# ATX_Adapter.net
KiCad netlist of a schematic drawn in EAGLE
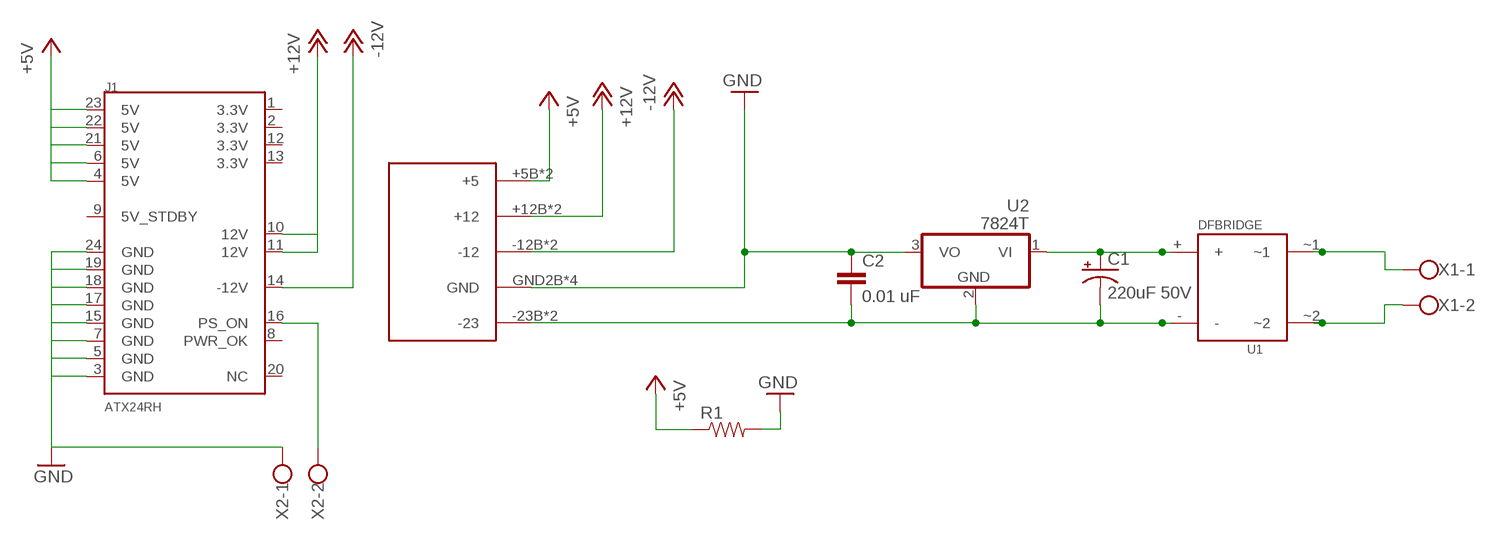
[diagram p0: schematic, sheet 1]

(export (version "E")
  (design (tool "Eeschema 10.0.6"))
  (components
    (comp (ref "C1")
      (value "220uF 50V")
      (footprint "eagle-import:CPOL-RADIAL-100UF-25V")
      (libsource (lib "eagle-import") (part "CAP_POLPTH1"))
    )
    (comp (ref "C2")
      (value "0.01 uF")
      (footprint "eagle-import:CAP-PTH-SMALLEZ")
      (libsource (lib "eagle-import") (part "CAPEZ"))
    )
    (comp (ref "J1")
      (value "ATX24RH")
      (footprint "eagle-import:ATX24_RIGHT_ANGLE")
      (libsource (lib "eagle-import") (part "ATX24RH"))
    )
    (comp (ref "R1")
      (value "RESISTORPTH-2W")
      (footprint "eagle-import:AXIAL-0.8")
      (libsource (lib "eagle-import") (part "RESISTORPTH-2W"))
    )
    (comp (ref "U$1")
      (value "VT100POWER")
      (footprint "eagle-import:VT100POWER")
      (libsource (lib "eagle-import") (part "VT100POWER"))
    )
    (comp (ref "U1")
      (value "DFBRIDGE")
      (footprint "eagle-import:DFBRIDGE")
      (libsource (lib "eagle-import") (part "DFBRIDGE"))
    )
    (comp (ref "U2")
      (value "7824T")
      (footprint "eagle-import:TO220H")
      (libsource (lib "eagle-import") (part "78T24"))
    )
    (comp (ref "X1")
      (value "W237-102")
      (footprint "eagle-import:W237-102")
      (fields (field (name "MPN") "237-102"))
      (libsource (lib "eagle-import") (part "W237-102"))
    )
    (comp (ref "X2")
      (value "W237-102")
      (footprint "eagle-import:W237-102")
      (fields (field (name "MPN") "237-102"))
      (libsource (lib "eagle-import") (part "W237-102"))
    )
  )
  (nets
    (net (code "1") (name "+5V") (class "Default")
      (node (ref "J1") (pin "21") (pinfunction "5V_21") (pintype "bidirectional"))
      (node (ref "J1") (pin "22") (pinfunction "5V_22") (pintype "bidirectional"))
      (node (ref "J1") (pin "23") (pinfunction "5V_23") (pintype "bidirectional"))
      (node (ref "J1") (pin "4") (pinfunction "5V_4") (pintype "bidirectional"))
      (node (ref "J1") (pin "6") (pinfunction "5V_6") (pintype "bidirectional"))
      (node (ref "R1") (pin "P$1") (pinfunction "1_P$1") (pintype "passive"))
      (node (ref "U$1") (pin "+5B") (pinfunction "+5_+5B") (pintype "bidirectional"))
      (node (ref "U$1") (pin "+5T") (pinfunction "+5_+5T") (pintype "bidirectional"))
    )
    (net (code "2") (name "+12V") (class "Default")
      (node (ref "J1") (pin "10") (pinfunction "12V_10") (pintype "bidirectional"))
      (node (ref "J1") (pin "11") (pinfunction "12V_11") (pintype "bidirectional"))
      (node (ref "U$1") (pin "+12B") (pinfunction "+12_+12B") (pintype "bidirectional"))
      (node (ref "U$1") (pin "+12T") (pinfunction "+12_+12T") (pintype "bidirectional"))
    )
    (net (code "3") (name "-12V") (class "Default")
      (node (ref "J1") (pin "14") (pinfunction "-12V_14") (pintype "bidirectional"))
      (node (ref "U$1") (pin "-12B") (pinfunction "-12_-12B") (pintype "bidirectional"))
      (node (ref "U$1") (pin "-12T") (pinfunction "-12_-12T") (pintype "bidirectional"))
    )
    (net (code "4") (name "GND") (class "Default")
      (node (ref "C2") (pin "1") (pinfunction "1_1") (pintype "passive"))
      (node (ref "J1") (pin "15") (pinfunction "GND_15") (pintype "bidirectional"))
      (node (ref "J1") (pin "17") (pinfunction "GND_17") (pintype "bidirectional"))
      (node (ref "J1") (pin "18") (pinfunction "GND_18") (pintype "bidirectional"))
      (node (ref "J1") (pin "19") (pinfunction "GND_19") (pintype "bidirectional"))
      (node (ref "J1") (pin "24") (pinfunction "GND_24") (pintype "bidirectional"))
      (node (ref "J1") (pin "3") (pinfunction "GND_3") (pintype "bidirectional"))
      (node (ref "J1") (pin "5") (pinfunction "GND_5") (pintype "bidirectional"))
      (node (ref "J1") (pin "7") (pinfunction "GND_7") (pintype "bidirectional"))
      (node (ref "R1") (pin "P$2") (pinfunction "2_P$2") (pintype "passive"))
      (node (ref "U$1") (pin "GND2B") (pinfunction "GND_GND2B") (pintype "bidirectional"))
      (node (ref "U$1") (pin "GNDB1") (pinfunction "GND_GNDB1") (pintype "bidirectional"))
      (node (ref "U$1") (pin "GNDT1") (pinfunction "GND_GNDT1") (pintype "bidirectional"))
      (node (ref "U$1") (pin "GNDT2") (pinfunction "GND_GNDT2") (pintype "bidirectional"))
      (node (ref "U2") (pin "3") (pinfunction "VO_3") (pintype "passive"))
      (node (ref "X2") (pin "1") (pinfunction "KL_1") (pintype "passive"))
    )
    (net (code "5") (name "Net-(C1-+)") (class "Default")
      (node (ref "C1") (pin "1") (pinfunction "+_1") (pintype "passive"))
      (node (ref "U1") (pin "+") (pinfunction "+_+") (pintype "bidirectional"))
      (node (ref "U2") (pin "1") (pinfunction "VI_1") (pintype "input"))
    )
    (net (code "6") (name "Net-(C1--)") (class "Default")
      (node (ref "C1") (pin "2") (pinfunction "-_2") (pintype "passive"))
      (node (ref "C2") (pin "2") (pinfunction "2_2") (pintype "passive"))
      (node (ref "U$1") (pin "-23B") (pinfunction "-23_-23B") (pintype "bidirectional"))
      (node (ref "U$1") (pin "-23T") (pinfunction "-23_-23T") (pintype "bidirectional"))
      (node (ref "U1") (pin "-") (pinfunction "-_-") (pintype "bidirectional"))
      (node (ref "U2") (pin "2") (pinfunction "GND_2") (pintype "passive"))
    )
    (net (code "7") (name "Net-(J1-PS_ON)") (class "Default")
      (node (ref "J1") (pin "16") (pinfunction "PS_ON_16") (pintype "bidirectional"))
      (node (ref "X2") (pin "2") (pinfunction "KL_2") (pintype "passive"))
    )
    (net (code "8") (name "Net-(U1-~{1})") (class "Default")
      (node (ref "U1") (pin "~1") (pinfunction "~{1}_~1") (pintype "bidirectional"))
      (node (ref "X1") (pin "1") (pinfunction "KL_1") (pintype "passive"))
    )
    (net (code "9") (name "Net-(U1-~{2})") (class "Default")
      (node (ref "U1") (pin "~2") (pinfunction "~{2}_~2") (pintype "bidirectional"))
      (node (ref "X1") (pin "2") (pinfunction "KL_2") (pintype "passive"))
    )
    (net (code "10") (name "unconnected-(J1-3.3V-Pad1)") (class "Default")
      (node (ref "J1") (pin "1") (pinfunction "3.3V_1") (pintype "bidirectional"))
    )
    (net (code "11") (name "unconnected-(J1-3.3V-Pad2)") (class "Default")
      (node (ref "J1") (pin "2") (pinfunction "3.3V_2") (pintype "bidirectional"))
    )
    (net (code "12") (name "unconnected-(J1-3.3V-Pad12)") (class "Default")
      (node (ref "J1") (pin "12") (pinfunction "3.3V_12") (pintype "bidirectional"))
    )
    (net (code "13") (name "unconnected-(J1-3.3V-Pad13)") (class "Default")
      (node (ref "J1") (pin "13") (pinfunction "3.3V_13") (pintype "bidirectional"))
    )
    (net (code "14") (name "unconnected-(J1-5V_STDBY-Pad9)") (class "Default")
      (node (ref "J1") (pin "9") (pinfunction "5V_STDBY_9") (pintype "bidirectional"))
    )
    (net (code "15") (name "unconnected-(J1-NC-Pad20)") (class "Default")
      (node (ref "J1") (pin "20") (pinfunction "NC_20") (pintype "bidirectional"))
    )
    (net (code "16") (name "unconnected-(J1-PWR_OK-Pad8)") (class "Default")
      (node (ref "J1") (pin "8") (pinfunction "PWR_OK_8") (pintype "bidirectional"))
    )
  )
)
